# communication.net
KiCad netlist of a schematic drawn in Altium Designer
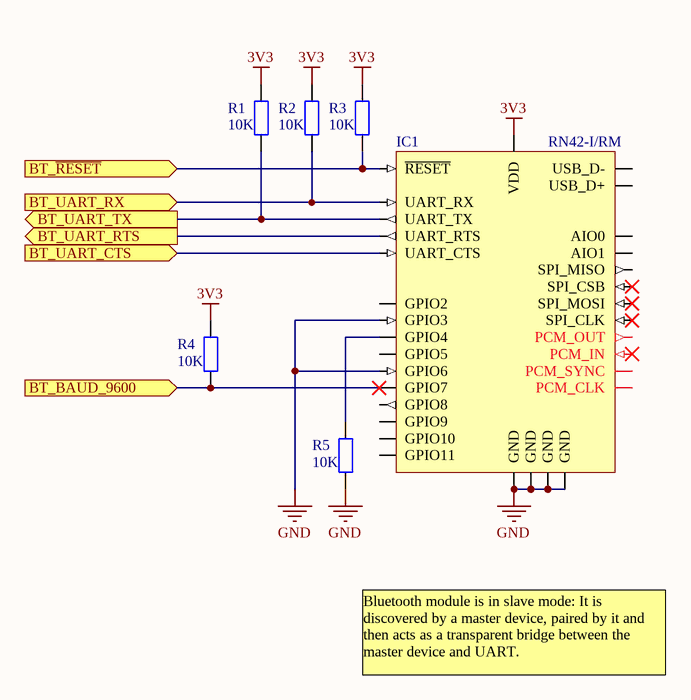
[diagram p0: communication.SchDoc]

(export (version "E")
  (design (tool "Eeschema 10.0.6"))
  (components
    (comp (ref "IC1")
      (value "RN42-I/RM")
      (footprint "RN42")
      (description "Bluetooth 2.1 module")
      (libsource (lib "Misc") (part "RN42"))
    )
    (comp (ref "R1")
      (value "10K")
      (footprint "TwoTerminal:1608[0603]_M")
      (description "Generic Resistor")
      (libsource (lib "Passive") (part "Resistor"))
    )
    (comp (ref "R2")
      (value "10K")
      (footprint "TwoTerminal:1608[0603]_M")
      (description "Generic Resistor")
      (libsource (lib "Passive") (part "Resistor"))
    )
    (comp (ref "R3")
      (value "10K")
      (footprint "TwoTerminal:1608[0603]_M")
      (description "Generic Resistor")
      (libsource (lib "Passive") (part "Resistor"))
    )
    (comp (ref "R4")
      (value "10K")
      (footprint "TwoTerminal:1608[0603]_M")
      (description "Generic Resistor")
      (libsource (lib "Passive") (part "Resistor"))
    )
    (comp (ref "R5")
      (value "10K")
      (footprint "TwoTerminal:1608[0603]_M")
      (description "Generic Resistor")
      (libsource (lib "Passive") (part "Resistor"))
    )
  )
  (nets
    (net (code "1") (name "/BT_BAUD_9600") (class "Default")
      (node (ref "IC1") (pin "4") (pinfunction "GPIO7_4") (pintype "bidirectional"))
      (node (ref "R4") (pin "1") (pinfunction "1_1") (pintype "passive"))
    )
    (net (code "2") (name "/BT_UART_CTS") (class "Default")
      (node (ref "IC1") (pin "16") (pinfunction "UART_CTS_16") (pintype "input"))
    )
    (net (code "3") (name "/BT_UART_RTS") (class "Default")
      (node (ref "IC1") (pin "15") (pinfunction "UART_RTS_15") (pintype "output"))
    )
    (net (code "4") (name "/BT_UART_RX") (class "Default")
      (node (ref "IC1") (pin "13") (pinfunction "UART_RX_13") (pintype "input"))
      (node (ref "R2") (pin "1") (pinfunction "1_1") (pintype "passive"))
    )
    (net (code "5") (name "/BT_UART_TX") (class "Default")
      (node (ref "IC1") (pin "14") (pinfunction "UART_TX_14") (pintype "output"))
      (node (ref "R1") (pin "1") (pinfunction "1_1") (pintype "passive"))
    )
    (net (code "6") (name "/BT_~{RESET}") (class "Default")
      (node (ref "IC1") (pin "5") (pinfunction "~{RESET}_5") (pintype "input"))
      (node (ref "R3") (pin "1") (pinfunction "1_1") (pintype "passive"))
    )
    (net (code "7") (name "3V3") (class "Default")
      (node (ref "IC1") (pin "11") (pinfunction "VDD_11") (pintype "power_in"))
      (node (ref "R1") (pin "2") (pinfunction "2_2") (pintype "passive"))
      (node (ref "R2") (pin "2") (pinfunction "2_2") (pintype "passive"))
      (node (ref "R3") (pin "2") (pinfunction "2_2") (pintype "passive"))
      (node (ref "R4") (pin "2") (pinfunction "2_2") (pintype "passive"))
    )
    (net (code "8") (name "GND") (class "Default")
      (node (ref "IC1") (pin "1") (pinfunction "GND_1") (pintype "power_in"))
      (node (ref "IC1") (pin "12") (pinfunction "GND_12") (pintype "power_in"))
      (node (ref "IC1") (pin "20") (pinfunction "GPIO3_20") (pintype "input"))
      (node (ref "IC1") (pin "28") (pinfunction "GND_28") (pintype "power_in"))
      (node (ref "IC1") (pin "29") (pinfunction "GND_29") (pintype "power_in"))
      (node (ref "IC1") (pin "3") (pinfunction "GPIO6_3") (pintype "input"))
      (node (ref "R5") (pin "1") (pinfunction "1_1") (pintype "passive"))
    )
    (net (code "9") (name "Net-(IC1-GPIO4)") (class "Default")
      (node (ref "IC1") (pin "22") (pinfunction "GPIO4_22") (pintype "bidirectional"))
      (node (ref "R5") (pin "2") (pinfunction "2_2") (pintype "passive"))
    )
    (net (code "10") (name "unconnected-(IC1-AIO0-Pad30)") (class "Default")
      (node (ref "IC1") (pin "30") (pinfunction "AIO0_30") (pintype "bidirectional"))
    )
    (net (code "11") (name "unconnected-(IC1-AIO1-Pad35)") (class "Default")
      (node (ref "IC1") (pin "35") (pinfunction "AIO1_35") (pintype "bidirectional"))
    )
    (net (code "12") (name "unconnected-(IC1-GPIO2-Pad19)") (class "Default")
      (node (ref "IC1") (pin "19") (pinfunction "GPIO2_19") (pintype "bidirectional"))
    )
    (net (code "13") (name "unconnected-(IC1-GPIO5-Pad21)") (class "Default")
      (node (ref "IC1") (pin "21") (pinfunction "GPIO5_21") (pintype "bidirectional"))
    )
    (net (code "14") (name "unconnected-(IC1-GPIO8-Pad31)") (class "Default")
      (node (ref "IC1") (pin "31") (pinfunction "GPIO8_31") (pintype "output"))
    )
    (net (code "15") (name "unconnected-(IC1-GPIO9-Pad32)") (class "Default")
      (node (ref "IC1") (pin "32") (pinfunction "GPIO9_32") (pintype "bidirectional"))
    )
    (net (code "16") (name "unconnected-(IC1-GPIO10-Pad33)") (class "Default")
      (node (ref "IC1") (pin "33") (pinfunction "GPIO10_33") (pintype "bidirectional"))
    )
    (net (code "17") (name "unconnected-(IC1-GPIO11-Pad34)") (class "Default")
      (node (ref "IC1") (pin "34") (pinfunction "GPIO11_34") (pintype "bidirectional"))
    )
    (net (code "18") (name "unconnected-(IC1-PCM_CLK-Pad7)") (class "Default")
      (node (ref "IC1") (pin "7") (pinfunction "PCM_CLK_7") (pintype "bidirectional"))
    )
    (net (code "19") (name "unconnected-(IC1-PCM_IN-Pad9)") (class "Default")
      (node (ref "IC1") (pin "9") (pinfunction "PCM_IN_9") (pintype "input+no_connect"))
    )
    (net (code "20") (name "unconnected-(IC1-PCM_OUT-Pad10)") (class "Default")
      (node (ref "IC1") (pin "10") (pinfunction "PCM_OUT_10") (pintype "output"))
    )
    (net (code "21") (name "unconnected-(IC1-PCM_SYNC-Pad8)") (class "Default")
      (node (ref "IC1") (pin "8") (pinfunction "PCM_SYNC_8") (pintype "bidirectional"))
    )
    (net (code "22") (name "unconnected-(IC1-SPI_CLK-Pad6)") (class "Default")
      (node (ref "IC1") (pin "6") (pinfunction "SPI_CLK_6") (pintype "input+no_connect"))
    )
    (net (code "23") (name "unconnected-(IC1-SPI_CSB-Pad23)") (class "Default")
      (node (ref "IC1") (pin "23") (pinfunction "SPI_CSB_23") (pintype "input+no_connect"))
    )
    (net (code "24") (name "unconnected-(IC1-SPI_MISO-Pad24)") (class "Default")
      (node (ref "IC1") (pin "24") (pinfunction "SPI_MISO_24") (pintype "output"))
    )
    (net (code "25") (name "unconnected-(IC1-SPI_MOSI-Pad2)") (class "Default")
      (node (ref "IC1") (pin "2") (pinfunction "SPI_MOSI_2") (pintype "input+no_connect"))
    )
    (net (code "26") (name "unconnected-(IC1-USB_D+-Pad17)") (class "Default")
      (node (ref "IC1") (pin "17") (pinfunction "USB_D+_17") (pintype "bidirectional"))
    )
    (net (code "27") (name "unconnected-(IC1-USB_D--Pad18)") (class "Default")
      (node (ref "IC1") (pin "18") (pinfunction "USB_D-_18") (pintype "bidirectional"))
    )
  )
)
